# 1-Schematic_ACS2STM-alt-DB19.net
KiCad netlist of a schematic drawn in EasyEDA
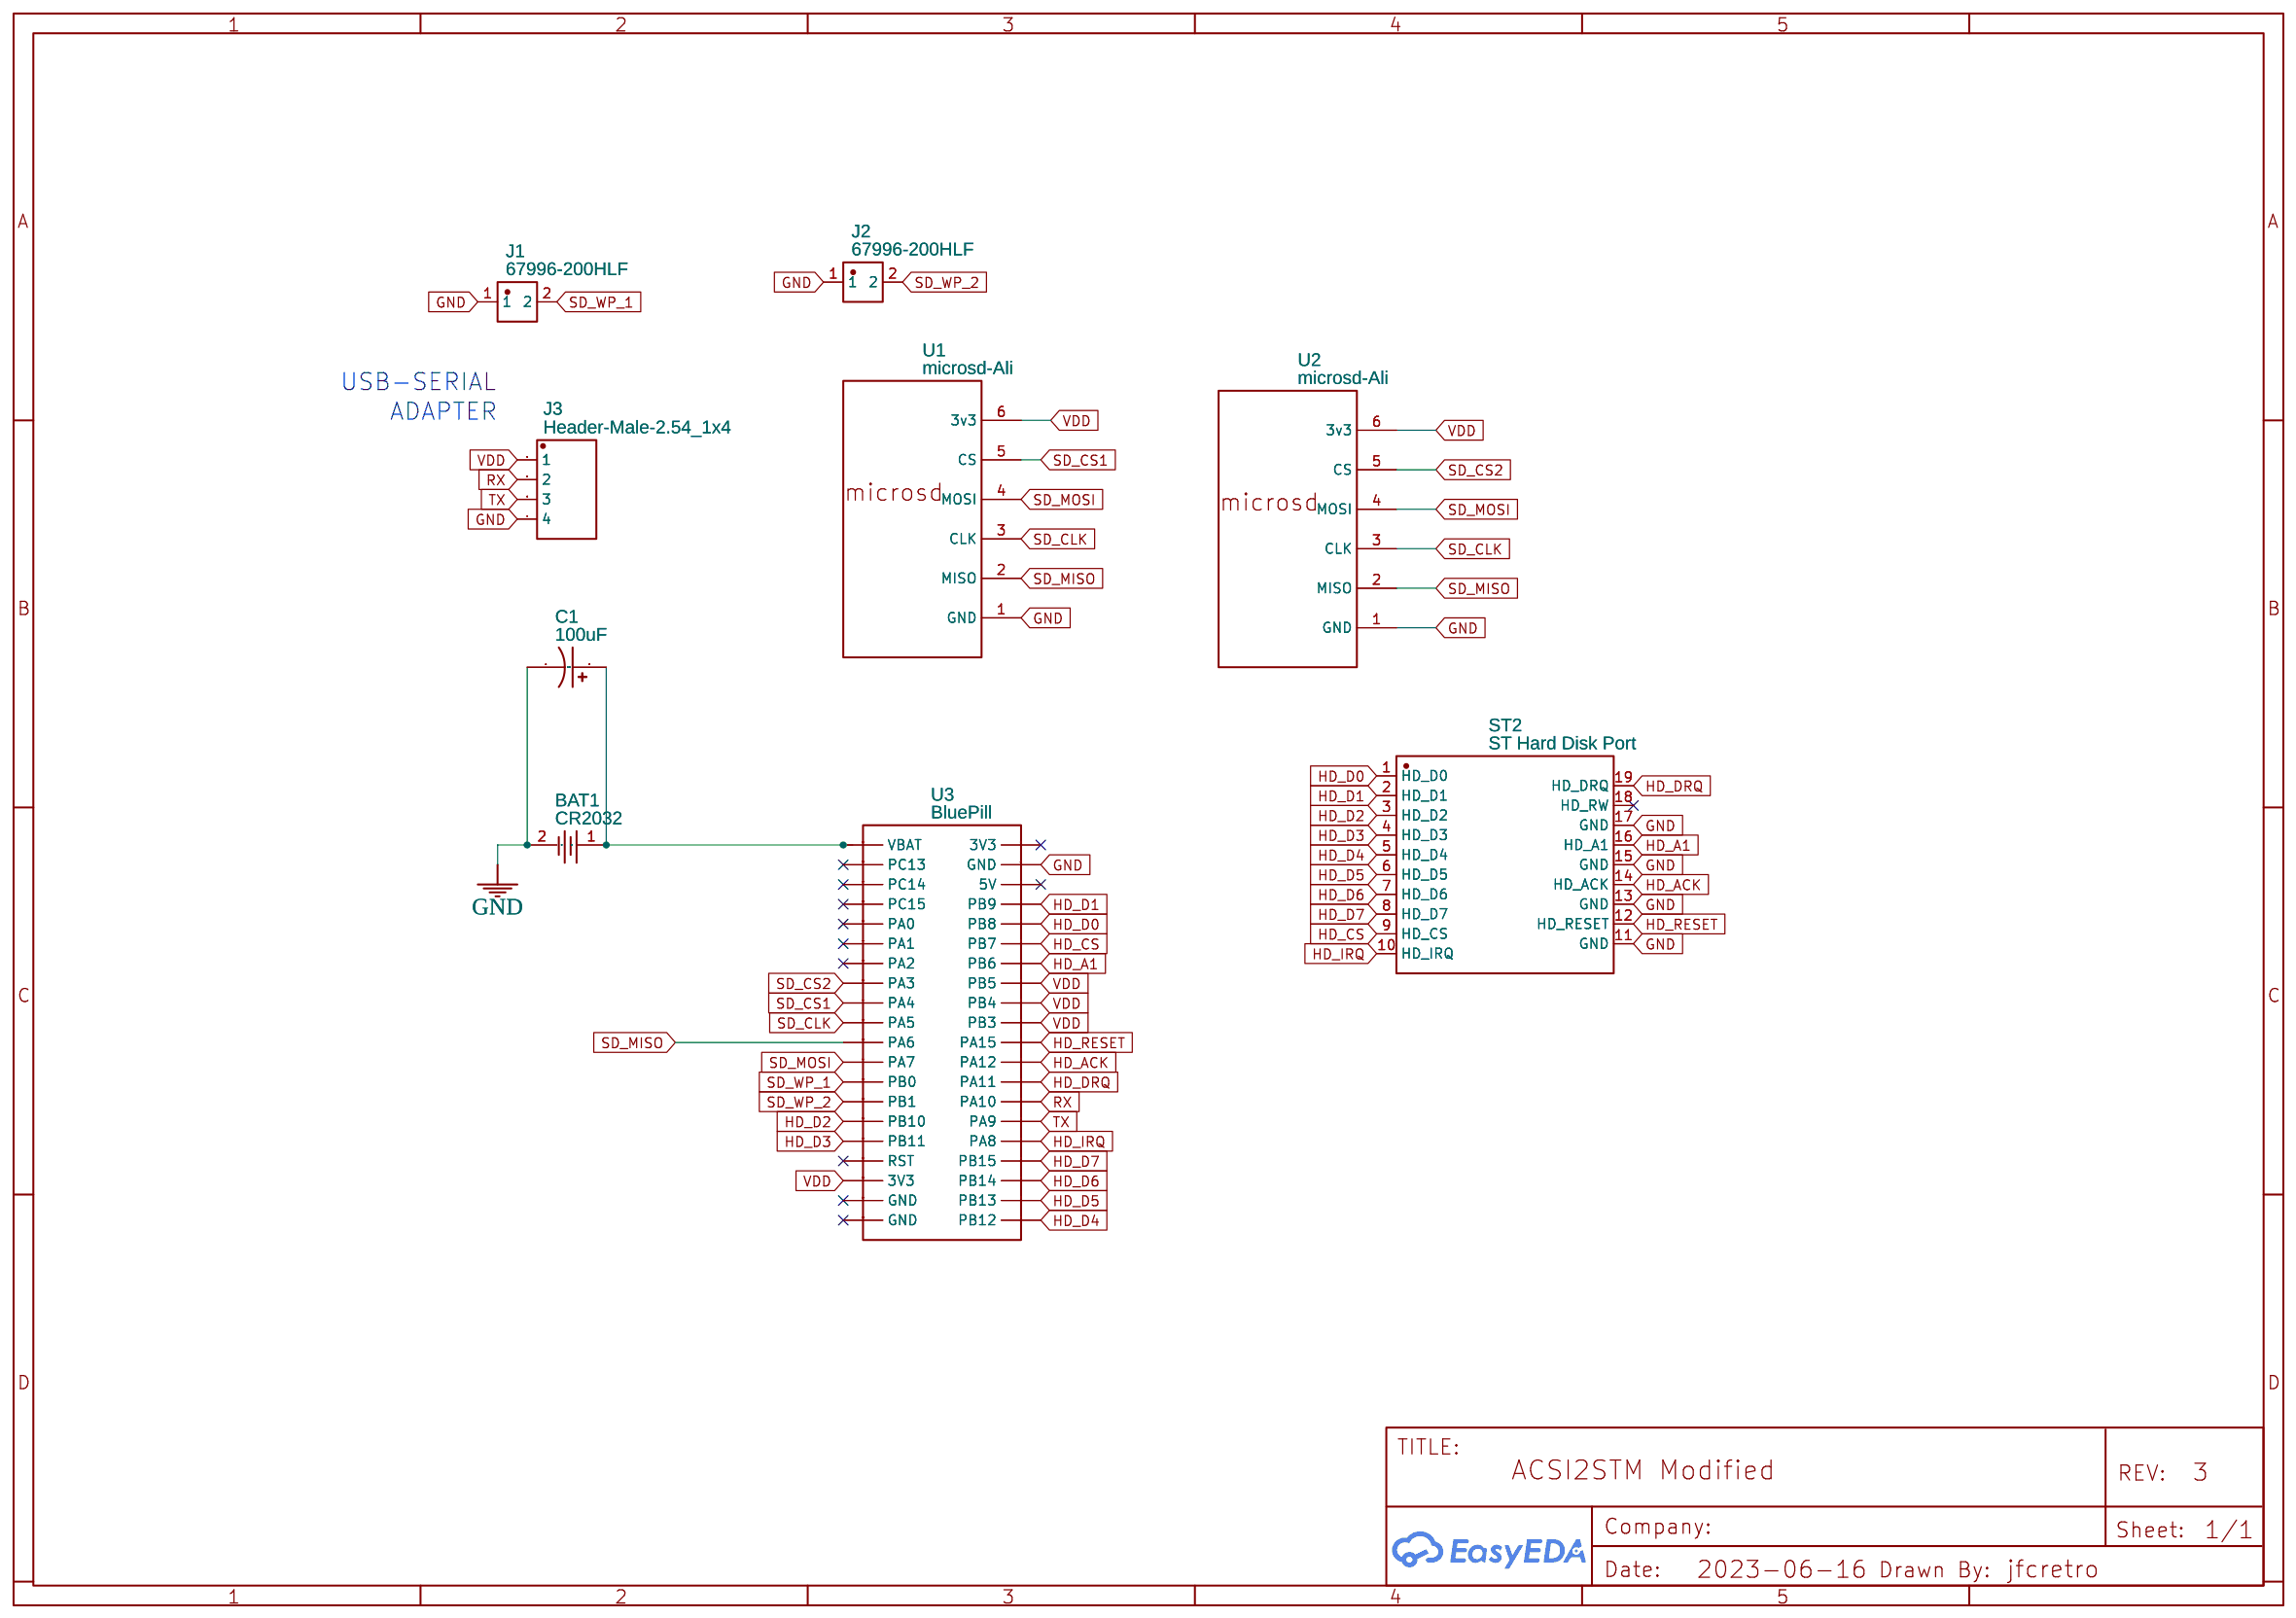
[diagram p0: schematic sheet]

(export (version "E")
  (design (tool "Eeschema 10.0.6"))
  (components
    (comp (ref "BAT1")
      (value "CR2032")
      (fields (field (name "BOM_Supplier Part") "C9900007674"))
      (libsource (lib "") (part "CR2032_C9900007674"))
    )
    (comp (ref "C1") (value "100uF") (libsource (lib "") (part "CE_TH_D6.3×F2.5_US")))
    (comp (ref "J1")
      (value "67996-200HLF")
      (fields (field (name "BOM_Supplier Part") "C236045"))
      (libsource (lib "") (part "67996-200HLF"))
    )
    (comp (ref "J2")
      (value "67996-200HLF")
      (fields (field (name "BOM_Supplier Part") "C236045"))
      (libsource (lib "") (part "67996-200HLF"))
    )
    (comp (ref "J3")
      (value "Header-Male-2.54_1x4")
      (fields
        (field (name "BOM_Manufacturer Part") "B-2100S04P-A110")
        (field (name "BOM_Supplier Part") "C124378")
      )
      (libsource (lib "") (part "Header-Male-2.54_1x4"))
    )
    (comp (ref "ST2") (value "ST Hard Disk Port") (libsource (lib "") (part "ST Hard Disk Port")))
    (comp (ref "U1") (value "microsd-Ali") (libsource (lib "") (part "microsd-Ali")))
    (comp (ref "U2") (value "microsd-Ali") (libsource (lib "") (part "microsd-Ali")))
    (comp (ref "U3") (value "BluePill") (libsource (lib "") (part "BluePill")))
  )
  (nets
    (net (code "1") (name "GND") (class "Default")
      (node (ref "BAT1") (pin "2") (pinfunction "2_2") (pintype "input"))
      (node (ref "C1") (pin "2") (pinfunction "2_2") (pintype "unspecified"))
      (node (ref "J1") (pin "1") (pinfunction "1_1") (pintype "unspecified"))
      (node (ref "J2") (pin "1") (pinfunction "1_1") (pintype "unspecified"))
      (node (ref "J3") (pin "4") (pinfunction "4_4") (pintype "unspecified"))
      (node (ref "ST2") (pin "11") (pinfunction "GND_11") (pintype "unspecified"))
      (node (ref "ST2") (pin "13") (pinfunction "GND_13") (pintype "unspecified"))
      (node (ref "ST2") (pin "15") (pinfunction "GND_15") (pintype "unspecified"))
      (node (ref "ST2") (pin "17") (pinfunction "GND_17") (pintype "unspecified"))
      (node (ref "U1") (pin "1") (pinfunction "GND_1") (pintype "unspecified"))
      (node (ref "U2") (pin "1") (pinfunction "GND_1") (pintype "unspecified"))
      (node (ref "U3") (pin "GND_3") (pinfunction "GND_GND_3") (pintype "unspecified"))
    )
    (net (code "2") (name "HD_A1") (class "Default")
      (node (ref "ST2") (pin "16") (pinfunction "HD_A1_16") (pintype "unspecified"))
      (node (ref "U3") (pin "PB6") (pinfunction "PB6_PB6") (pintype "unspecified"))
    )
    (net (code "3") (name "HD_ACK") (class "Default")
      (node (ref "ST2") (pin "14") (pinfunction "HD_ACK_14") (pintype "unspecified"))
      (node (ref "U3") (pin "PA12") (pinfunction "PA12_PA12") (pintype "unspecified"))
    )
    (net (code "4") (name "HD_CS") (class "Default")
      (node (ref "ST2") (pin "9") (pinfunction "HD_CS_9") (pintype "unspecified"))
      (node (ref "U3") (pin "PB7") (pinfunction "PB7_PB7") (pintype "unspecified"))
    )
    (net (code "5") (name "HD_D0") (class "Default")
      (node (ref "ST2") (pin "1") (pinfunction "HD_D0_1") (pintype "unspecified"))
      (node (ref "U3") (pin "PB8") (pinfunction "PB8_PB8") (pintype "unspecified"))
    )
    (net (code "6") (name "HD_D1") (class "Default")
      (node (ref "ST2") (pin "2") (pinfunction "HD_D1_2") (pintype "unspecified"))
      (node (ref "U3") (pin "PB9") (pinfunction "PB9_PB9") (pintype "unspecified"))
    )
    (net (code "7") (name "HD_D2") (class "Default")
      (node (ref "ST2") (pin "3") (pinfunction "HD_D2_3") (pintype "unspecified"))
      (node (ref "U3") (pin "PB10") (pinfunction "PB10_PB10") (pintype "unspecified"))
    )
    (net (code "8") (name "HD_D3") (class "Default")
      (node (ref "ST2") (pin "4") (pinfunction "HD_D3_4") (pintype "unspecified"))
      (node (ref "U3") (pin "PB11") (pinfunction "PB11_PB11") (pintype "unspecified"))
    )
    (net (code "9") (name "HD_D4") (class "Default")
      (node (ref "ST2") (pin "5") (pinfunction "HD_D4_5") (pintype "unspecified"))
      (node (ref "U3") (pin "PB12") (pinfunction "PB12_PB12") (pintype "unspecified"))
    )
    (net (code "10") (name "HD_D5") (class "Default")
      (node (ref "ST2") (pin "6") (pinfunction "HD_D5_6") (pintype "unspecified"))
      (node (ref "U3") (pin "PB13") (pinfunction "PB13_PB13") (pintype "unspecified"))
    )
    (net (code "11") (name "HD_D6") (class "Default")
      (node (ref "ST2") (pin "7") (pinfunction "HD_D6_7") (pintype "unspecified"))
      (node (ref "U3") (pin "PB14") (pinfunction "PB14_PB14") (pintype "unspecified"))
    )
    (net (code "12") (name "HD_D7") (class "Default")
      (node (ref "ST2") (pin "8") (pinfunction "HD_D7_8") (pintype "unspecified"))
      (node (ref "U3") (pin "PB15") (pinfunction "PB15_PB15") (pintype "unspecified"))
    )
    (net (code "13") (name "HD_DRQ") (class "Default")
      (node (ref "ST2") (pin "19") (pinfunction "HD_DRQ_19") (pintype "unspecified"))
      (node (ref "U3") (pin "PA11") (pinfunction "PA11_PA11") (pintype "unspecified"))
    )
    (net (code "14") (name "HD_IRQ") (class "Default")
      (node (ref "ST2") (pin "10") (pinfunction "HD_IRQ_10") (pintype "unspecified"))
      (node (ref "U3") (pin "PA8") (pinfunction "PA8_PA8") (pintype "unspecified"))
    )
    (net (code "15") (name "HD_RESET") (class "Default")
      (node (ref "ST2") (pin "12") (pinfunction "HD_RESET_12") (pintype "unspecified"))
      (node (ref "U3") (pin "PA15") (pinfunction "PA15_PA15") (pintype "unspecified"))
    )
    (net (code "16") (name "Net-(BAT1-Pad1)") (class "Default")
      (node (ref "BAT1") (pin "1") (pinfunction "1_1") (pintype "input"))
      (node (ref "C1") (pin "1") (pinfunction "1_1") (pintype "unspecified"))
      (node (ref "U3") (pin "VBAT") (pinfunction "VBAT_VBAT") (pintype "unspecified"))
    )
    (net (code "17") (name "RX") (class "Default")
      (node (ref "J3") (pin "2") (pinfunction "2_2") (pintype "unspecified"))
      (node (ref "U3") (pin "PA10") (pinfunction "PA10_PA10") (pintype "unspecified"))
    )
    (net (code "18") (name "SD_CLK") (class "Default")
      (node (ref "U1") (pin "3") (pinfunction "CLK_3") (pintype "unspecified"))
      (node (ref "U2") (pin "3") (pinfunction "CLK_3") (pintype "unspecified"))
      (node (ref "U3") (pin "PA5") (pinfunction "PA5_PA5") (pintype "unspecified"))
    )
    (net (code "19") (name "SD_CS1") (class "Default")
      (node (ref "U1") (pin "5") (pinfunction "CS_5") (pintype "unspecified"))
      (node (ref "U3") (pin "PA4") (pinfunction "PA4_PA4") (pintype "unspecified"))
    )
    (net (code "20") (name "SD_CS2") (class "Default")
      (node (ref "U2") (pin "5") (pinfunction "CS_5") (pintype "unspecified"))
      (node (ref "U3") (pin "PA3") (pinfunction "PA3_PA3") (pintype "unspecified"))
    )
    (net (code "21") (name "SD_MISO") (class "Default")
      (node (ref "U1") (pin "2") (pinfunction "MISO_2") (pintype "unspecified"))
      (node (ref "U2") (pin "2") (pinfunction "MISO_2") (pintype "unspecified"))
      (node (ref "U3") (pin "PA6") (pinfunction "PA6_PA6") (pintype "unspecified"))
    )
    (net (code "22") (name "SD_MOSI") (class "Default")
      (node (ref "U1") (pin "4") (pinfunction "MOSI_4") (pintype "unspecified"))
      (node (ref "U2") (pin "4") (pinfunction "MOSI_4") (pintype "unspecified"))
      (node (ref "U3") (pin "PA7") (pinfunction "PA7_PA7") (pintype "unspecified"))
    )
    (net (code "23") (name "SD_WP_1") (class "Default")
      (node (ref "J1") (pin "2") (pinfunction "2_2") (pintype "unspecified"))
      (node (ref "U3") (pin "PB0") (pinfunction "PB0_PB0") (pintype "unspecified"))
    )
    (net (code "24") (name "SD_WP_2") (class "Default")
      (node (ref "J2") (pin "2") (pinfunction "2_2") (pintype "unspecified"))
      (node (ref "U3") (pin "PB1") (pinfunction "PB1_PB1") (pintype "unspecified"))
    )
    (net (code "25") (name "TX") (class "Default")
      (node (ref "J3") (pin "3") (pinfunction "3_3") (pintype "unspecified"))
      (node (ref "U3") (pin "PA9") (pinfunction "PA9_PA9") (pintype "unspecified"))
    )
    (net (code "26") (name "VDD") (class "Default")
      (node (ref "J3") (pin "1") (pinfunction "1_1") (pintype "unspecified"))
      (node (ref "U1") (pin "6") (pinfunction "3v3_6") (pintype "unspecified"))
      (node (ref "U2") (pin "6") (pinfunction "3v3_6") (pintype "unspecified"))
      (node (ref "U3") (pin "3V3_1") (pinfunction "3V3_3V3_1") (pintype "unspecified"))
      (node (ref "U3") (pin "PB3") (pinfunction "PB3_PB3") (pintype "unspecified"))
      (node (ref "U3") (pin "PB4") (pinfunction "PB4_PB4") (pintype "unspecified"))
      (node (ref "U3") (pin "PB5") (pinfunction "PB5_PB5") (pintype "unspecified"))
    )
    (net (code "27") (name "unconnected-(ST2-HD_RW-Pad18)") (class "Default")
      (node (ref "ST2") (pin "18") (pinfunction "HD_RW_18") (pintype "unspecified+no_connect"))
    )
    (net (code "28") (name "unconnected-(U3-3V3-Pad3V3_2)") (class "Default")
      (node (ref "U3") (pin "3V3_2") (pinfunction "3V3_3V3_2") (pintype "unspecified+no_connect"))
    )
    (net (code "29") (name "unconnected-(U3-GND-PadGND_1)") (class "Default")
      (node (ref "U3") (pin "GND_1") (pinfunction "GND_GND_1") (pintype "unspecified+no_connect"))
    )
    (net (code "30") (name "unconnected-(U3-GND-PadGND_2)") (class "Default")
      (node (ref "U3") (pin "GND_2") (pinfunction "GND_GND_2") (pintype "unspecified+no_connect"))
    )
    (net (code "31") (name "unconnected-(U3-Pad5V)") (class "Default")
      (node (ref "U3") (pin "5V") (pinfunction "5V_5V") (pintype "unspecified+no_connect"))
    )
    (net (code "32") (name "unconnected-(U3-PadPA0)") (class "Default")
      (node (ref "U3") (pin "PA0") (pinfunction "PA0_PA0") (pintype "unspecified+no_connect"))
    )
    (net (code "33") (name "unconnected-(U3-PadPA1)") (class "Default")
      (node (ref "U3") (pin "PA1") (pinfunction "PA1_PA1") (pintype "unspecified+no_connect"))
    )
    (net (code "34") (name "unconnected-(U3-PadPA2)") (class "Default")
      (node (ref "U3") (pin "PA2") (pinfunction "PA2_PA2") (pintype "unspecified+no_connect"))
    )
    (net (code "35") (name "unconnected-(U3-PadPC13)") (class "Default")
      (node (ref "U3") (pin "PC13") (pinfunction "PC13_PC13") (pintype "unspecified+no_connect"))
    )
    (net (code "36") (name "unconnected-(U3-PadPC14)") (class "Default")
      (node (ref "U3") (pin "PC14") (pinfunction "PC14_PC14") (pintype "unspecified+no_connect"))
    )
    (net (code "37") (name "unconnected-(U3-PadPC15)") (class "Default")
      (node (ref "U3") (pin "PC15") (pinfunction "PC15_PC15") (pintype "unspecified+no_connect"))
    )
    (net (code "38") (name "unconnected-(U3-PadRST)") (class "Default")
      (node (ref "U3") (pin "RST") (pinfunction "RST_RST") (pintype "unspecified+no_connect"))
    )
  )
)
